# processor.net
KiCad netlist of a schematic drawn in Altium Designer
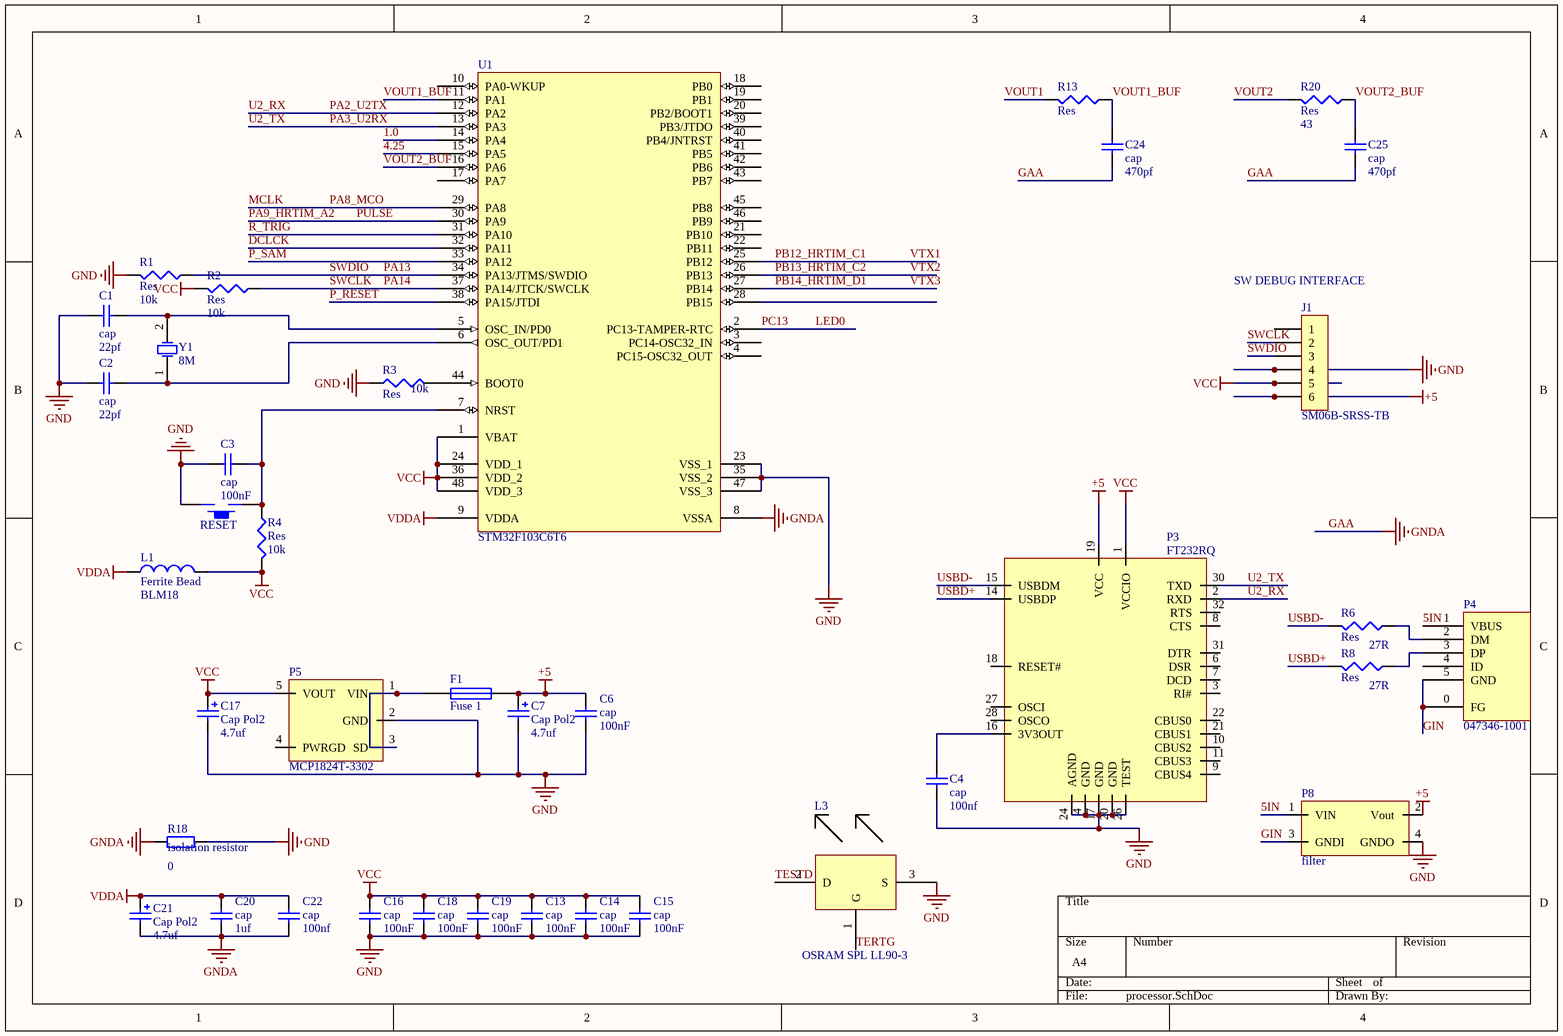
[diagram p0: processor.SchDoc]

(export (version "E")
  (design (tool "Eeschema 10.0.6"))
  (components
    (comp (ref "C1")
      (value "cap")
      (footprint "J1-0603")
      (description "Capacitor (Semiconductor SIM Model)")
      (fields (field (name "ALTIUM_VALUE") "22pf") (field (name "PUBLISHER") "Altium Limited"))
      (libsource (lib "Miscellaneous Devices") (part "Cap Semi"))
    )
    (comp (ref "C2")
      (value "cap")
      (footprint "J1-0603")
      (description "Capacitor (Semiconductor SIM Model)")
      (fields (field (name "ALTIUM_VALUE") "22pf") (field (name "PUBLISHER") "Altium Limited"))
      (libsource (lib "Miscellaneous Devices") (part "Cap Semi"))
    )
    (comp (ref "C3")
      (value "cap")
      (footprint "J1-0603")
      (description "Capacitor (Semiconductor SIM Model)")
      (fields (field (name "ALTIUM_VALUE") "100nF") (field (name "PUBLISHER") "Altium Limited"))
      (libsource (lib "Miscellaneous Devices") (part "Cap Semi"))
    )
    (comp (ref "C4")
      (value "cap")
      (footprint "J1-0603")
      (description "Capacitor (Semiconductor SIM Model)")
      (fields (field (name "ALTIUM_VALUE") "100nf") (field (name "PUBLISHER") "Altium Limited"))
      (libsource (lib "Miscellaneous Devices") (part "Cap Semi"))
    )
    (comp (ref "C6")
      (value "cap")
      (footprint "J1-0603")
      (description "Capacitor (Semiconductor SIM Model)")
      (fields (field (name "ALTIUM_VALUE") "100nF") (field (name "PUBLISHER") "Altium Limited"))
      (libsource (lib "Miscellaneous Devices") (part "Cap Semi"))
    )
    (comp (ref "C7")
      (value "Cap Pol2")
      (footprint "C1206+")
      (description "Polarized Capacitor (Axial)")
      (fields (field (name "ALTIUM_VALUE") "4.7uf") (field (name "PUBLISHER") "Altium Limited"))
      (libsource (lib "Miscellaneous Devices") (part "Cap Pol2"))
    )
    (comp (ref "C13")
      (value "cap")
      (footprint "J1-0603")
      (description "Capacitor (Semiconductor SIM Model)")
      (fields (field (name "ALTIUM_VALUE") "100nF") (field (name "PUBLISHER") "Altium Limited"))
      (libsource (lib "Miscellaneous Devices") (part "Cap Semi"))
    )
    (comp (ref "C14")
      (value "cap")
      (footprint "J1-0603")
      (description "Capacitor (Semiconductor SIM Model)")
      (fields (field (name "ALTIUM_VALUE") "100nF") (field (name "PUBLISHER") "Altium Limited"))
      (libsource (lib "Miscellaneous Devices") (part "Cap Semi"))
    )
    (comp (ref "C15")
      (value "cap")
      (footprint "J1-0603")
      (description "Capacitor (Semiconductor SIM Model)")
      (fields (field (name "ALTIUM_VALUE") "100nF") (field (name "PUBLISHER") "Altium Limited"))
      (libsource (lib "Miscellaneous Devices") (part "Cap Semi"))
    )
    (comp (ref "C16")
      (value "cap")
      (footprint "J1-0603")
      (description "Capacitor (Semiconductor SIM Model)")
      (fields (field (name "ALTIUM_VALUE") "100nF") (field (name "PUBLISHER") "Altium Limited"))
      (libsource (lib "Miscellaneous Devices") (part "Cap Semi"))
    )
    (comp (ref "C17")
      (value "Cap Pol2")
      (footprint "C1206+")
      (description "Polarized Capacitor (Axial)")
      (fields (field (name "ALTIUM_VALUE") "4.7uf") (field (name "PUBLISHER") "Altium Limited"))
      (libsource (lib "Miscellaneous Devices") (part "Cap Pol2"))
    )
    (comp (ref "C18")
      (value "cap")
      (footprint "J1-0603")
      (description "Capacitor (Semiconductor SIM Model)")
      (fields (field (name "ALTIUM_VALUE") "100nF") (field (name "PUBLISHER") "Altium Limited"))
      (libsource (lib "Miscellaneous Devices") (part "Cap Semi"))
    )
    (comp (ref "C19")
      (value "cap")
      (footprint "J1-0603")
      (description "Capacitor (Semiconductor SIM Model)")
      (fields (field (name "ALTIUM_VALUE") "100nF") (field (name "PUBLISHER") "Altium Limited"))
      (libsource (lib "Miscellaneous Devices") (part "Cap Semi"))
    )
    (comp (ref "C20")
      (value "cap")
      (footprint "J1-0603")
      (description "Capacitor (Semiconductor SIM Model)")
      (fields (field (name "ALTIUM_VALUE") "1uf") (field (name "PUBLISHER") "Altium Limited"))
      (libsource (lib "Miscellaneous Devices") (part "Cap Semi"))
    )
    (comp (ref "C21")
      (value "Cap Pol2")
      (footprint "C1206+")
      (description "Polarized Capacitor (Axial)")
      (fields (field (name "ALTIUM_VALUE") "4.7uf") (field (name "PUBLISHER") "Altium Limited"))
      (libsource (lib "Miscellaneous Devices") (part "Cap Pol2"))
    )
    (comp (ref "C22")
      (value "cap")
      (footprint "J1-0603")
      (description "Capacitor (Semiconductor SIM Model)")
      (fields (field (name "ALTIUM_VALUE") "100nf") (field (name "PUBLISHER") "Altium Limited"))
      (libsource (lib "Miscellaneous Devices") (part "Cap Semi"))
    )
    (comp (ref "C24")
      (value "cap")
      (footprint "J1-0603")
      (description "Capacitor (Semiconductor SIM Model)")
      (fields (field (name "ALTIUM_VALUE") "470pf") (field (name "PUBLISHER") "Altium Limited"))
      (libsource (lib "Miscellaneous Devices") (part "Cap Semi"))
    )
    (comp (ref "C25")
      (value "cap")
      (footprint "J1-0603")
      (description "Capacitor (Semiconductor SIM Model)")
      (fields (field (name "ALTIUM_VALUE") "470pf") (field (name "PUBLISHER") "Altium Limited"))
      (libsource (lib "Miscellaneous Devices") (part "Cap Semi"))
    )
    (comp (ref "F1")
      (value "Fuse 1")
      (footprint "J1-0603")
      (description "Fuse")
      (fields (field (name "PUBLISHER") "Altium Limited"))
      (libsource (lib "Miscellaneous Devices") (part "Fuse 1"))
    )
    (comp (ref "J1")
      (value "SM06B-SRSS-TB")
      (footprint "SM06B-SRSS-TB")
      (description "Connector")
      (fields (field (name "MANUFACTURER") "JST"))
      (libsource (lib "JST_SH") (part "SM06B-SRSS-TB"))
    )
    (comp (ref "L1")
      (value "Ferrite Bead")
      (footprint "J1-0603")
      (description "Inductor")
      (fields (field (name "ALTIUM_VALUE") "BLM18") (field (name "PUBLISHER") "Altium Limited"))
      (libsource (lib "Miscellaneous Devices") (part "Inductor"))
    )
    (comp (ref "L3")
      (value "OSRAM SPL LL90-3")
      (footprint "SPLLL")
      (libsource (lib "jskschemlib") (part "SPL_laser"))
    )
    (comp (ref "P3") (value "FT232RQ") (footprint "QFN32") (libsource (lib "jskschemlib") (part "FT232RQ")))
    (comp (ref "P4")
      (value "047346-1001")
      (footprint "047346-1001")
      (description "Micro USB B Connector")
      (fields (field (name "MANUFACTURER") "Molex"))
      (libsource (lib "Molex") (part "047346-1001"))
    )
    (comp (ref "P5")
      (value "MCP1824T-3302")
      (footprint "SOT-23")
      (libsource (lib "jskschemlib") (part "VOLTREG"))
    )
    (comp (ref "P8") (value "filter") (footprint "bx025") (libsource (lib "jskschemlib") (part "filter")))
    (comp (ref "R1")
      (value "Res")
      (footprint "J1-0603")
      (description "Resistor")
      (fields (field (name "ALTIUM_VALUE") "10k") (field (name "PUBLISHER") "Altium Limited"))
      (libsource (lib "Miscellaneous Devices") (part "Res3"))
    )
    (comp (ref "R2")
      (value "Res")
      (footprint "J1-0603")
      (description "Resistor")
      (fields (field (name "ALTIUM_VALUE") "10k") (field (name "PUBLISHER") "Altium Limited"))
      (libsource (lib "Miscellaneous Devices") (part "Res3"))
    )
    (comp (ref "R3")
      (value "Res")
      (footprint "J1-0603")
      (description "Resistor")
      (fields (field (name "ALTIUM_VALUE") "10k") (field (name "PUBLISHER") "Altium Limited"))
      (libsource (lib "Miscellaneous Devices") (part "Res3"))
    )
    (comp (ref "R4")
      (value "Res")
      (footprint "J1-0603")
      (description "Resistor")
      (fields (field (name "ALTIUM_VALUE") "10k") (field (name "PUBLISHER") "Altium Limited"))
      (libsource (lib "Miscellaneous Devices") (part "Res3"))
    )
    (comp (ref "R6")
      (value "Res")
      (footprint "J1-0603")
      (description "Resistor")
      (fields (field (name "ALTIUM_VALUE") "27R") (field (name "PUBLISHER") "Altium Limited"))
      (libsource (lib "Miscellaneous Devices") (part "Res3"))
    )
    (comp (ref "R8")
      (value "Res")
      (footprint "J1-0603")
      (description "Resistor")
      (fields (field (name "ALTIUM_VALUE") "27R") (field (name "PUBLISHER") "Altium Limited"))
      (libsource (lib "Miscellaneous Devices") (part "Res3"))
    )
    (comp (ref "R13")
      (value "Res")
      (footprint "J1-0603")
      (description "Resistor")
      (fields (field (name "PUBLISHER") "Altium Limited"))
      (libsource (lib "Miscellaneous Devices") (part "Res3"))
    )
    (comp (ref "R18")
      (value "isolation resistor")
      (footprint "J1-0603")
      (description "Resistor")
      (fields (field (name "ALTIUM_VALUE") "0") (field (name "PUBLISHER") "Altium Limited"))
      (libsource (lib "Miscellaneous Devices") (part "Res2"))
    )
    (comp (ref "R20")
      (value "Res")
      (footprint "J1-0603")
      (description "Resistor")
      (fields (field (name "ALTIUM_VALUE") "43") (field (name "PUBLISHER") "Altium Limited"))
      (libsource (lib "Miscellaneous Devices") (part "Res3"))
    )
    (comp (ref "RESET")
      (value "KEY_M")
      (footprint "TSWITCH")
      (libsource (lib "2014ﾄ鷭STM32F4 Exploerｿｪｷ｢ｰ・V1.4_ｽﾌｳﾌﾂﾒｸﾄｰ觸EXPLORER") (part "KEY_M"))
    )
    (comp (ref "U1")
      (value "STM32F103C6T6")
      (footprint "LQFP48_L")
      (description "STM32 ARM-based 32-bit MCU with 32 Kbytes Flash, 48-pin LQFP, Industrial Temperature")
      (fields (field (name "PUBLISHER") "*"))
      (libsource (lib "ST Microcontroller 32-Bit STM32 SCH") (part "STM32F103C6T6"))
    )
    (comp (ref "Y1")
      (value "8M")
      (footprint "XTALSMD8")
      (description "Crystal Oscillator")
      (fields (field (name "PUBLISHER") "Altium Limited"))
      (libsource (lib "Miscellaneous Devices") (part "XTAL"))
    )
  )
  (nets
    (net (code "1") (name "+5") (class "Default")
      (node (ref "C6") (pin "2") (pinfunction "2_2") (pintype "passive"))
      (node (ref "C7") (pin "1") (pinfunction "1_1") (pintype "passive"))
      (node (ref "F1") (pin "2") (pinfunction "2_2") (pintype "passive"))
      (node (ref "J1") (pin "6") (pinfunction "6_6") (pintype "passive"))
      (node (ref "P3") (pin "19") (pinfunction "VCC_19") (pintype "passive"))
      (node (ref "P8") (pin "2") (pinfunction "Vout_2") (pintype "passive"))
    )
    (net (code "2") (name "/1.0") (class "Default")
      (node (ref "U1") (pin "14") (pinfunction "PA4_14") (pintype "bidirectional"))
    )
    (net (code "3") (name "/4.25") (class "Default")
      (node (ref "U1") (pin "15") (pinfunction "PA5_15") (pintype "bidirectional"))
    )
    (net (code "4") (name "/5IN") (class "Default")
      (node (ref "P4") (pin "1") (pinfunction "VBUS_1") (pintype "passive"))
      (node (ref "P8") (pin "1") (pinfunction "VIN_1") (pintype "passive"))
    )
    (net (code "5") (name "/DCLCK") (class "Default")
      (node (ref "U1") (pin "32") (pinfunction "PA11_32") (pintype "bidirectional"))
    )
    (net (code "6") (name "/GIN") (class "Default")
      (node (ref "P4") (pin "0") (pinfunction "FG_0") (pintype "passive"))
      (node (ref "P4") (pin "5") (pinfunction "GND_5") (pintype "passive"))
      (node (ref "P8") (pin "3") (pinfunction "GNDI_3") (pintype "passive"))
    )
    (net (code "7") (name "/LED0") (class "Default")
      (node (ref "U1") (pin "2") (pinfunction "PC13-TAMPER-RTC_2") (pintype "bidirectional"))
    )
    (net (code "8") (name "/MCLK") (class "Default")
      (node (ref "U1") (pin "29") (pinfunction "PA8_29") (pintype "bidirectional"))
    )
    (net (code "9") (name "/PA2_U2TX") (class "Default")
      (node (ref "P3") (pin "2") (pinfunction "RXD_2") (pintype "passive"))
      (node (ref "U1") (pin "12") (pinfunction "PA2_12") (pintype "bidirectional"))
    )
    (net (code "10") (name "/PA3_U2RX") (class "Default")
      (node (ref "P3") (pin "30") (pinfunction "TXD_30") (pintype "passive"))
      (node (ref "U1") (pin "13") (pinfunction "PA3_13") (pintype "bidirectional"))
    )
    (net (code "11") (name "/PA9_HRTIM_A2") (class "Default")
      (node (ref "U1") (pin "30") (pinfunction "PA9_30") (pintype "bidirectional"))
    )
    (net (code "12") (name "/PA13") (class "Default")
      (node (ref "J1") (pin "3") (pinfunction "3_3") (pintype "passive"))
      (node (ref "R1") (pin "1") (pinfunction "1_1") (pintype "passive"))
      (node (ref "U1") (pin "34") (pinfunction "PA13/JTMS/SWDIO_34") (pintype "bidirectional"))
    )
    (net (code "13") (name "/PA14") (class "Default")
      (node (ref "J1") (pin "2") (pinfunction "2_2") (pintype "passive"))
      (node (ref "R2") (pin "1") (pinfunction "1_1") (pintype "passive"))
      (node (ref "U1") (pin "37") (pinfunction "PA14/JTCK/SWCLK_37") (pintype "bidirectional"))
    )
    (net (code "14") (name "/PB12_HRTIM_C1") (class "Default")
      (node (ref "U1") (pin "25") (pinfunction "PB12_25") (pintype "bidirectional"))
    )
    (net (code "15") (name "/PB13_HRTIM_C2") (class "Default")
      (node (ref "U1") (pin "26") (pinfunction "PB13_26") (pintype "bidirectional"))
    )
    (net (code "16") (name "/PB14_HRTIM_D1") (class "Default")
      (node (ref "U1") (pin "27") (pinfunction "PB14_27") (pintype "bidirectional"))
    )
    (net (code "17") (name "/P_RESET") (class "Default")
      (node (ref "U1") (pin "38") (pinfunction "PA15/JTDI_38") (pintype "bidirectional"))
    )
    (net (code "18") (name "/P_SAM") (class "Default")
      (node (ref "U1") (pin "33") (pinfunction "PA12_33") (pintype "bidirectional"))
    )
    (net (code "19") (name "/R_TRIG") (class "Default")
      (node (ref "U1") (pin "31") (pinfunction "PA10_31") (pintype "bidirectional"))
    )
    (net (code "20") (name "/TERTG") (class "Default")
      (node (ref "L3") (pin "1") (pinfunction "G_1") (pintype "passive"))
    )
    (net (code "21") (name "/TESTD") (class "Default")
      (node (ref "L3") (pin "2") (pinfunction "D_2") (pintype "passive"))
    )
    (net (code "22") (name "/USBD+") (class "Default")
      (node (ref "P3") (pin "14") (pinfunction "USBDP_14") (pintype "passive"))
      (node (ref "R8") (pin "2") (pinfunction "2_2") (pintype "passive"))
    )
    (net (code "23") (name "/USBD-") (class "Default")
      (node (ref "P3") (pin "15") (pinfunction "USBDM_15") (pintype "passive"))
      (node (ref "R6") (pin "2") (pinfunction "2_2") (pintype "passive"))
    )
    (net (code "24") (name "/VOUT1") (class "Default")
      (node (ref "R13") (pin "2") (pinfunction "2_2") (pintype "passive"))
    )
    (net (code "25") (name "/VOUT1_BUF") (class "Default")
      (node (ref "C24") (pin "2") (pinfunction "2_2") (pintype "passive"))
      (node (ref "R13") (pin "1") (pinfunction "1_1") (pintype "passive"))
      (node (ref "U1") (pin "11") (pinfunction "PA1_11") (pintype "bidirectional"))
    )
    (net (code "26") (name "/VOUT2") (class "Default")
      (node (ref "R20") (pin "2") (pinfunction "2_2") (pintype "passive"))
    )
    (net (code "27") (name "/VOUT2_BUF") (class "Default")
      (node (ref "C25") (pin "2") (pinfunction "2_2") (pintype "passive"))
      (node (ref "R20") (pin "1") (pinfunction "1_1") (pintype "passive"))
      (node (ref "U1") (pin "16") (pinfunction "PA6_16") (pintype "bidirectional"))
    )
    (net (code "28") (name "GND") (class "Default")
      (node (ref "C1") (pin "1") (pinfunction "1_1") (pintype "passive"))
      (node (ref "C13") (pin "1") (pinfunction "1_1") (pintype "passive"))
      (node (ref "C14") (pin "1") (pinfunction "1_1") (pintype "passive"))
      (node (ref "C15") (pin "1") (pinfunction "1_1") (pintype "passive"))
      (node (ref "C16") (pin "1") (pinfunction "1_1") (pintype "passive"))
      (node (ref "C17") (pin "2") (pinfunction "2_2") (pintype "passive"))
      (node (ref "C18") (pin "1") (pinfunction "1_1") (pintype "passive"))
      (node (ref "C19") (pin "1") (pinfunction "1_1") (pintype "passive"))
      (node (ref "C2") (pin "1") (pinfunction "1_1") (pintype "passive"))
      (node (ref "C3") (pin "1") (pinfunction "1_1") (pintype "passive"))
      (node (ref "C4") (pin "1") (pinfunction "1_1") (pintype "passive"))
      (node (ref "C6") (pin "1") (pinfunction "1_1") (pintype "passive"))
      (node (ref "C7") (pin "2") (pinfunction "2_2") (pintype "passive"))
      (node (ref "J1") (pin "4") (pinfunction "4_4") (pintype "passive"))
      (node (ref "L3") (pin "3") (pinfunction "S_3") (pintype "passive"))
      (node (ref "P3") (pin "17") (pinfunction "GND_17") (pintype "passive"))
      (node (ref "P3") (pin "20") (pinfunction "GND_20") (pintype "passive"))
      (node (ref "P3") (pin "24") (pinfunction "AGND_24") (pintype "passive"))
      (node (ref "P3") (pin "26") (pinfunction "TEST_26") (pintype "passive"))
      (node (ref "P3") (pin "4") (pinfunction "GND_4") (pintype "passive"))
      (node (ref "P5") (pin "2") (pinfunction "GND_2") (pintype "passive"))
      (node (ref "P8") (pin "4") (pinfunction "GNDO_4") (pintype "passive"))
      (node (ref "R1") (pin "2") (pinfunction "2_2") (pintype "passive"))
      (node (ref "R18") (pin "2") (pinfunction "2_2") (pintype "passive"))
      (node (ref "R3") (pin "1") (pinfunction "1_1") (pintype "passive"))
      (node (ref "RESET") (pin "2") (pinfunction "2_2") (pintype "passive"))
      (node (ref "U1") (pin "23") (pinfunction "VSS_1_23") (pintype "power_in"))
      (node (ref "U1") (pin "35") (pinfunction "VSS_2_35") (pintype "power_in"))
      (node (ref "U1") (pin "47") (pinfunction "VSS_3_47") (pintype "power_in"))
    )
    (net (code "29") (name "GNDA") (class "Default")
      (node (ref "C20") (pin "1") (pinfunction "1_1") (pintype "passive"))
      (node (ref "C21") (pin "2") (pinfunction "2_2") (pintype "passive"))
      (node (ref "C22") (pin "1") (pinfunction "1_1") (pintype "passive"))
      (node (ref "C24") (pin "1") (pinfunction "1_1") (pintype "passive"))
      (node (ref "C25") (pin "1") (pinfunction "1_1") (pintype "passive"))
      (node (ref "R18") (pin "1") (pinfunction "1_1") (pintype "passive"))
      (node (ref "U1") (pin "8") (pinfunction "VSSA_8") (pintype "power_in"))
    )
    (net (code "30") (name "Net-(P3-3V3OUT)") (class "Default")
      (node (ref "C4") (pin "2") (pinfunction "2_2") (pintype "passive"))
      (node (ref "P3") (pin "16") (pinfunction "3V3OUT_16") (pintype "passive"))
    )
    (net (code "31") (name "Net-(P4-DM)") (class "Default")
      (node (ref "P4") (pin "2") (pinfunction "DM_2") (pintype "passive"))
      (node (ref "R6") (pin "1") (pinfunction "1_1") (pintype "passive"))
    )
    (net (code "32") (name "Net-(P4-DP)") (class "Default")
      (node (ref "P4") (pin "3") (pinfunction "DP_3") (pintype "passive"))
      (node (ref "R8") (pin "1") (pinfunction "1_1") (pintype "passive"))
    )
    (net (code "33") (name "Net-(P5-SD)") (class "Default")
      (node (ref "F1") (pin "1") (pinfunction "1_1") (pintype "passive"))
      (node (ref "P5") (pin "1") (pinfunction "VIN_1") (pintype "passive"))
      (node (ref "P5") (pin "3") (pinfunction "SD_3") (pintype "passive"))
    )
    (net (code "34") (name "Net-(U1-BOOT0)") (class "Default")
      (node (ref "R3") (pin "2") (pinfunction "2_2") (pintype "passive"))
      (node (ref "U1") (pin "44") (pinfunction "BOOT0_44") (pintype "input"))
    )
    (net (code "35") (name "Net-(U1-NRST)") (class "Default")
      (node (ref "C3") (pin "2") (pinfunction "2_2") (pintype "passive"))
      (node (ref "R4") (pin "1") (pinfunction "1_1") (pintype "passive"))
      (node (ref "RESET") (pin "1") (pinfunction "1_1") (pintype "passive"))
      (node (ref "U1") (pin "7") (pinfunction "NRST_7") (pintype "bidirectional"))
    )
    (net (code "36") (name "Net-(U1-OSC_IN{slash}PD0)") (class "Default")
      (node (ref "C1") (pin "2") (pinfunction "2_2") (pintype "passive"))
      (node (ref "U1") (pin "5") (pinfunction "OSC_IN/PD0_5") (pintype "input"))
      (node (ref "Y1") (pin "2") (pinfunction "OSC2_2") (pintype "passive"))
    )
    (net (code "37") (name "Net-(U1-OSC_OUT{slash}PD1)") (class "Default")
      (node (ref "C2") (pin "2") (pinfunction "2_2") (pintype "passive"))
      (node (ref "U1") (pin "6") (pinfunction "OSC_OUT/PD1_6") (pintype "output"))
      (node (ref "Y1") (pin "1") (pinfunction "OSC1_1") (pintype "passive"))
    )
    (net (code "38") (name "VCC") (class "Default")
      (node (ref "C13") (pin "2") (pinfunction "2_2") (pintype "passive"))
      (node (ref "C14") (pin "2") (pinfunction "2_2") (pintype "passive"))
      (node (ref "C15") (pin "2") (pinfunction "2_2") (pintype "passive"))
      (node (ref "C16") (pin "2") (pinfunction "2_2") (pintype "passive"))
      (node (ref "C17") (pin "1") (pinfunction "1_1") (pintype "passive"))
      (node (ref "C18") (pin "2") (pinfunction "2_2") (pintype "passive"))
      (node (ref "C19") (pin "2") (pinfunction "2_2") (pintype "passive"))
      (node (ref "J1") (pin "5") (pinfunction "5_5") (pintype "passive"))
      (node (ref "L1") (pin "2") (pinfunction "2_2") (pintype "passive"))
      (node (ref "P3") (pin "1") (pinfunction "VCCIO_1") (pintype "passive"))
      (node (ref "P5") (pin "5") (pinfunction "VOUT_5") (pintype "passive"))
      (node (ref "R2") (pin "2") (pinfunction "2_2") (pintype "passive"))
      (node (ref "R4") (pin "2") (pinfunction "2_2") (pintype "passive"))
      (node (ref "U1") (pin "1") (pinfunction "VBAT_1") (pintype "power_in"))
      (node (ref "U1") (pin "24") (pinfunction "VDD_1_24") (pintype "power_in"))
      (node (ref "U1") (pin "36") (pinfunction "VDD_2_36") (pintype "power_in"))
      (node (ref "U1") (pin "48") (pinfunction "VDD_3_48") (pintype "power_in"))
    )
    (net (code "39") (name "VDDA") (class "Default")
      (node (ref "C20") (pin "2") (pinfunction "2_2") (pintype "passive"))
      (node (ref "C21") (pin "1") (pinfunction "1_1") (pintype "passive"))
      (node (ref "C22") (pin "2") (pinfunction "2_2") (pintype "passive"))
      (node (ref "L1") (pin "1") (pinfunction "1_1") (pintype "passive"))
      (node (ref "U1") (pin "9") (pinfunction "VDDA_9") (pintype "power_in"))
    )
    (net (code "40") (name "unconnected-(J1-Pad1)") (class "Default")
      (node (ref "J1") (pin "1") (pinfunction "1_1") (pintype "passive"))
    )
    (net (code "41") (name "unconnected-(P3-CBUS0-Pad22)") (class "Default")
      (node (ref "P3") (pin "22") (pinfunction "CBUS0_22") (pintype "passive"))
    )
    (net (code "42") (name "unconnected-(P3-CBUS1-Pad21)") (class "Default")
      (node (ref "P3") (pin "21") (pinfunction "CBUS1_21") (pintype "passive"))
    )
    (net (code "43") (name "unconnected-(P3-CBUS2-Pad10)") (class "Default")
      (node (ref "P3") (pin "10") (pinfunction "CBUS2_10") (pintype "passive"))
    )
    (net (code "44") (name "unconnected-(P3-CBUS3-Pad11)") (class "Default")
      (node (ref "P3") (pin "11") (pinfunction "CBUS3_11") (pintype "passive"))
    )
    (net (code "45") (name "unconnected-(P3-CBUS4-Pad9)") (class "Default")
      (node (ref "P3") (pin "9") (pinfunction "CBUS4_9") (pintype "passive"))
    )
    (net (code "46") (name "unconnected-(P3-CTS-Pad8)") (class "Default")
      (node (ref "P3") (pin "8") (pinfunction "CTS_8") (pintype "passive"))
    )
    (net (code "47") (name "unconnected-(P3-DCD-Pad7)") (class "Default")
      (node (ref "P3") (pin "7") (pinfunction "DCD_7") (pintype "passive"))
    )
    (net (code "48") (name "unconnected-(P3-DSR-Pad6)") (class "Default")
      (node (ref "P3") (pin "6") (pinfunction "DSR_6") (pintype "passive"))
    )
    (net (code "49") (name "unconnected-(P3-DTR-Pad31)") (class "Default")
      (node (ref "P3") (pin "31") (pinfunction "DTR_31") (pintype "passive"))
    )
    (net (code "50") (name "unconnected-(P3-OSCI-Pad27)") (class "Default")
      (node (ref "P3") (pin "27") (pinfunction "OSCI_27") (pintype "passive"))
    )
    (net (code "51") (name "unconnected-(P3-OSCO-Pad28)") (class "Default")
      (node (ref "P3") (pin "28") (pinfunction "OSCO_28") (pintype "passive"))
    )
    (net (code "52") (name "unconnected-(P3-RESET#-Pad18)") (class "Default")
      (node (ref "P3") (pin "18") (pinfunction "RESET#_18") (pintype "passive"))
    )
    (net (code "53") (name "unconnected-(P3-RI#-Pad3)") (class "Default")
      (node (ref "P3") (pin "3") (pinfunction "RI#_3") (pintype "passive"))
    )
    (net (code "54") (name "unconnected-(P3-RTS-Pad32)") (class "Default")
      (node (ref "P3") (pin "32") (pinfunction "RTS_32") (pintype "passive"))
    )
    (net (code "55") (name "unconnected-(P4-ID-Pad4)") (class "Default")
      (node (ref "P4") (pin "4") (pinfunction "ID_4") (pintype "passive"))
    )
    (net (code "56") (name "unconnected-(P5-PWRGD-Pad4)") (class "Default")
      (node (ref "P5") (pin "4") (pinfunction "PWRGD_4") (pintype "passive"))
    )
    (net (code "57") (name "unconnected-(U1-PA0-WKUP-Pad10)") (class "Default")
      (node (ref "U1") (pin "10") (pinfunction "PA0-WKUP_10") (pintype "bidirectional"))
    )
    (net (code "58") (name "unconnected-(U1-PA7-Pad17)") (class "Default")
      (node (ref "U1") (pin "17") (pinfunction "PA7_17") (pintype "bidirectional"))
    )
    (net (code "59") (name "unconnected-(U1-PB0-Pad18)") (class "Default")
      (node (ref "U1") (pin "18") (pinfunction "PB0_18") (pintype "bidirectional"))
    )
    (net (code "60") (name "unconnected-(U1-PB1-Pad19)") (class "Default")
      (node (ref "U1") (pin "19") (pinfunction "PB1_19") (pintype "bidirectional"))
    )
    (net (code "61") (name "unconnected-(U1-PB2{slash}BOOT1-Pad20)") (class "Default")
      (node (ref "U1") (pin "20") (pinfunction "PB2/BOOT1_20") (pintype "bidirectional"))
    )
    (net (code "62") (name "unconnected-(U1-PB3{slash}JTDO-Pad39)") (class "Default")
      (node (ref "U1") (pin "39") (pinfunction "PB3/JTDO_39") (pintype "bidirectional"))
    )
    (net (code "63") (name "unconnected-(U1-PB4{slash}JNTRST-Pad40)") (class "Default")
      (node (ref "U1") (pin "40") (pinfunction "PB4/JNTRST_40") (pintype "bidirectional"))
    )
    (net (code "64") (name "unconnected-(U1-PB5-Pad41)") (class "Default")
      (node (ref "U1") (pin "41") (pinfunction "PB5_41") (pintype "bidirectional"))
    )
    (net (code "65") (name "unconnected-(U1-PB6-Pad42)") (class "Default")
      (node (ref "U1") (pin "42") (pinfunction "PB6_42") (pintype "bidirectional"))
    )
    (net (code "66") (name "unconnected-(U1-PB7-Pad43)") (class "Default")
      (node (ref "U1") (pin "43") (pinfunction "PB7_43") (pintype "bidirectional"))
    )
    (net (code "67") (name "unconnected-(U1-PB8-Pad45)") (class "Default")
      (node (ref "U1") (pin "45") (pinfunction "PB8_45") (pintype "bidirectional"))
    )
    (net (code "68") (name "unconnected-(U1-PB9-Pad46)") (class "Default")
      (node (ref "U1") (pin "46") (pinfunction "PB9_46") (pintype "bidirectional"))
    )
    (net (code "69") (name "unconnected-(U1-PB10-Pad21)") (class "Default")
      (node (ref "U1") (pin "21") (pinfunction "PB10_21") (pintype "bidirectional"))
    )
    (net (code "70") (name "unconnected-(U1-PB11-Pad22)") (class "Default")
      (node (ref "U1") (pin "22") (pinfunction "PB11_22") (pintype "bidirectional"))
    )
    (net (code "71") (name "unconnected-(U1-PB15-Pad28)") (class "Default")
      (node (ref "U1") (pin "28") (pinfunction "PB15_28") (pintype "bidirectional"))
    )
    (net (code "72") (name "unconnected-(U1-PC14-OSC32_IN-Pad3)") (class "Default")
      (node (ref "U1") (pin "3") (pinfunction "PC14-OSC32_IN_3") (pintype "bidirectional"))
    )
    (net (code "73") (name "unconnected-(U1-PC15-OSC32_OUT-Pad4)") (class "Default")
      (node (ref "U1") (pin "4") (pinfunction "PC15-OSC32_OUT_4") (pintype "bidirectional"))
    )
  )
)
